# VREG_RT9166-12PVL.net
KiCad netlist of a schematic drawn in Altium Designer
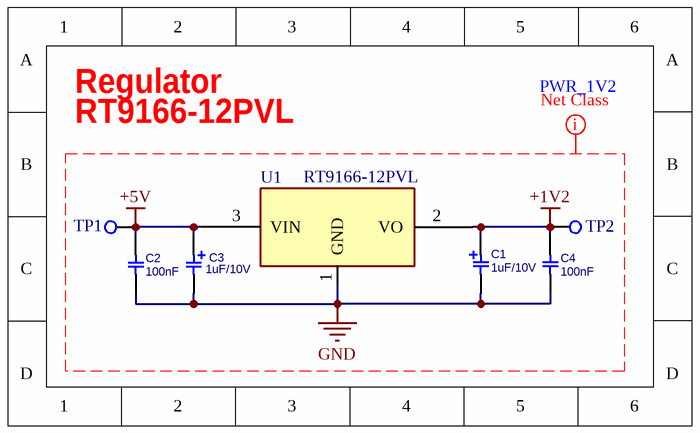
[diagram p0: VREG RT9166-12PVL.SchDoc]

(export (version "E")
  (design (tool "Eeschema 10.0.6"))
  (components
    (comp (ref "C1")
      (value "1uF/10V")
      (footprint "C_TN_3216")
      (description "CAP, SMD, TAN")
      (libsource (lib "Passive") (part "CAP_SMD_TAN"))
    )
    (comp (ref "C2")
      (value "100nF")
      (footprint "C0603S")
      (description "CAP, SMD, MLCC")
      (fields (field (name "MANF_P#") "MANF_PART#") (field (name "MANF") "Murata"))
      (libsource (lib "Passive") (part "CAP_SMD_MLCC"))
    )
    (comp (ref "C3")
      (value "1uF/10V")
      (footprint "C_TN_3216")
      (description "CAP, SMD, TAN")
      (libsource (lib "Passive") (part "CAP_SMD_TAN"))
    )
    (comp (ref "C4")
      (value "100nF")
      (footprint "C0603S")
      (description "CAP, SMD, MLCC")
      (fields (field (name "MANF_P#") "MANF_PART#") (field (name "MANF") "Murata"))
      (libsource (lib "Passive") (part "CAP_SMD_MLCC"))
    )
    (comp (ref "TP1")
      (value "Test Point")
      (footprint "TPSMD_C1")
      (libsource (lib "Passives") (part "Test Point"))
    )
    (comp (ref "TP2")
      (value "Test Point")
      (footprint "TPSMD_C1")
      (libsource (lib "Passives") (part "Test Point"))
    )
    (comp (ref "U1")
      (value "RT9166-12PVL")
      (footprint "SOT23_3")
      (description "REG, Linear, Fixed, 1.2v, 0.3A/0.6A, SOT23")
      (fields (field (name "MANF") "TI"))
      (libsource (lib "PW Components 97_481") (part "VREG_RT9166A-12PVL_SOT23"))
    )
  )
  (nets
    (net (code "1") (name "+1V2") (class "Default")
      (node (ref "C1") (pin "1") (pinfunction "1_1") (pintype "passive"))
      (node (ref "C4") (pin "1") (pinfunction "1_1") (pintype "passive"))
      (node (ref "TP2") (pin "1") (pinfunction "TP_1") (pintype "passive"))
      (node (ref "U1") (pin "2") (pinfunction "VO_2") (pintype "passive"))
    )
    (net (code "2") (name "+5V") (class "Default")
      (node (ref "C2") (pin "1") (pinfunction "1_1") (pintype "passive"))
      (node (ref "C3") (pin "1") (pinfunction "1_1") (pintype "passive"))
      (node (ref "TP1") (pin "1") (pinfunction "TP_1") (pintype "passive"))
      (node (ref "U1") (pin "3") (pinfunction "VIN_3") (pintype "passive"))
    )
    (net (code "3") (name "GND") (class "Default")
      (node (ref "C1") (pin "2") (pinfunction "2_2") (pintype "passive"))
      (node (ref "C2") (pin "2") (pinfunction "2_2") (pintype "passive"))
      (node (ref "C3") (pin "2") (pinfunction "2_2") (pintype "passive"))
      (node (ref "C4") (pin "2") (pinfunction "2_2") (pintype "passive"))
      (node (ref "U1") (pin "1") (pinfunction "GND_1") (pintype "passive"))
    )
  )
)
